# schematic.net
KiCad netlist of a schematic drawn in EAGLE
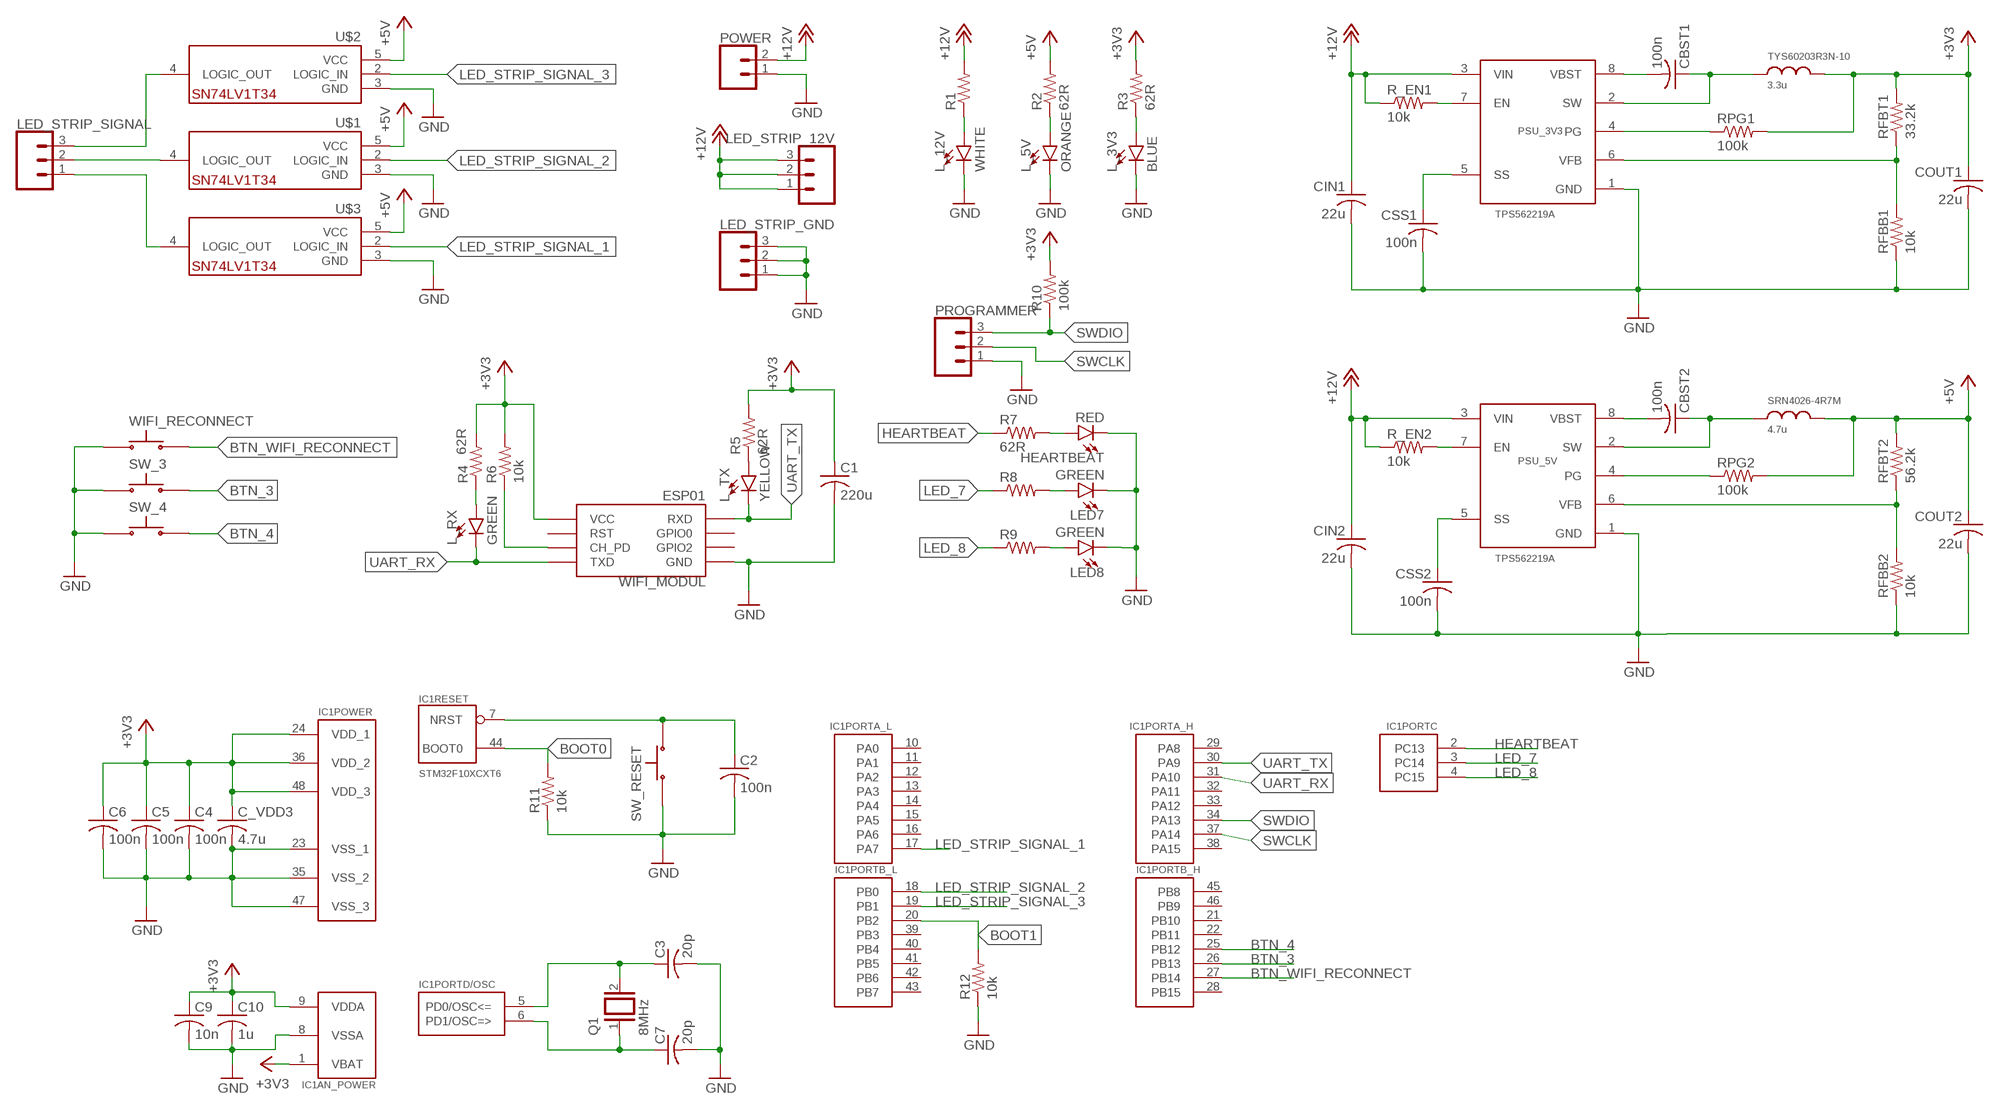
[diagram p0: schematic, sheet 1]

(export (version "E")
  (design (tool "Eeschema 10.0.6"))
  (components
    (comp (ref "C1")
      (value "220u")
      (footprint "eagle-import:C1206")
      (libsource (lib "eagle-import") (part "C-USC1206"))
    )
    (comp (ref "C2")
      (value "100n")
      (footprint "eagle-import:C1206")
      (libsource (lib "eagle-import") (part "C-USC1206"))
    )
    (comp (ref "C3")
      (value "20p")
      (footprint "eagle-import:C1206")
      (libsource (lib "eagle-import") (part "C-USC1206"))
    )
    (comp (ref "C4")
      (value "100n")
      (footprint "eagle-import:C1206")
      (libsource (lib "eagle-import") (part "C-USC1206"))
    )
    (comp (ref "C5")
      (value "100n")
      (footprint "eagle-import:C1206")
      (libsource (lib "eagle-import") (part "C-USC1206"))
    )
    (comp (ref "C6")
      (value "100n")
      (footprint "eagle-import:C1206")
      (libsource (lib "eagle-import") (part "C-USC1206"))
    )
    (comp (ref "C7")
      (value "20p")
      (footprint "eagle-import:C1206")
      (libsource (lib "eagle-import") (part "C-USC1206"))
    )
    (comp (ref "C9")
      (value "10n")
      (footprint "eagle-import:C1206")
      (libsource (lib "eagle-import") (part "C-USC1206"))
    )
    (comp (ref "C10")
      (value "1u")
      (footprint "eagle-import:C1206")
      (libsource (lib "eagle-import") (part "C-USC1206"))
    )
    (comp (ref "CBST1")
      (value "100n")
      (footprint "eagle-import:C1206")
      (libsource (lib "eagle-import") (part "C-USC1206"))
    )
    (comp (ref "CBST2")
      (value "100n")
      (footprint "eagle-import:C1206")
      (libsource (lib "eagle-import") (part "C-USC1206"))
    )
    (comp (ref "CIN1")
      (value "22u")
      (footprint "eagle-import:C1206")
      (libsource (lib "eagle-import") (part "C-USC1206"))
    )
    (comp (ref "CIN2")
      (value "22u")
      (footprint "eagle-import:C1206")
      (libsource (lib "eagle-import") (part "C-USC1206"))
    )
    (comp (ref "COUT1")
      (value "22u")
      (footprint "eagle-import:C1206")
      (libsource (lib "eagle-import") (part "C-USC1206"))
    )
    (comp (ref "COUT2")
      (value "22u")
      (footprint "eagle-import:C1206")
      (libsource (lib "eagle-import") (part "C-USC1206"))
    )
    (comp (ref "CSS1")
      (value "100n")
      (footprint "eagle-import:C1206")
      (libsource (lib "eagle-import") (part "C-USC1206"))
    )
    (comp (ref "CSS2")
      (value "100n")
      (footprint "eagle-import:C1206")
      (libsource (lib "eagle-import") (part "C-USC1206"))
    )
    (comp (ref "C_VDD3")
      (value "4.7u")
      (footprint "eagle-import:C1206")
      (libsource (lib "eagle-import") (part "C-USC1206"))
    )
    (comp (ref "HEARTBEAT")
      (value "RED")
      (footprint "eagle-import:LED-1206")
      (libsource (lib "eagle-import") (part "LED-GREEN1206"))
    )
    (comp (ref "IC1")
      (value "STM32F10XCXT6")
      (footprint "eagle-import:TQFP48")
      (libsource (lib "eagle-import") (part "STM32F10XCXT6"))
    )
    (comp (ref "LED7")
      (value "GREEN")
      (footprint "eagle-import:LED-1206")
      (libsource (lib "eagle-import") (part "LED-GREEN1206"))
    )
    (comp (ref "LED8")
      (value "GREEN")
      (footprint "eagle-import:LED-1206")
      (libsource (lib "eagle-import") (part "LED-GREEN1206"))
    )
    (comp (ref "LED_STRIP_12V")
      (value "CONN_03SCREW")
      (footprint "eagle-import:SCREWTERMINAL-3.5MM-3")
      (libsource (lib "eagle-import") (part "CONN_03SCREW"))
    )
    (comp (ref "LED_STRIP_GND")
      (value "CONN_03SCREW")
      (footprint "eagle-import:SCREWTERMINAL-3.5MM-3")
      (libsource (lib "eagle-import") (part "CONN_03SCREW"))
    )
    (comp (ref "LED_STRIP_SIGNAL")
      (value "CONN_03SCREW")
      (footprint "eagle-import:SCREWTERMINAL-3.5MM-3")
      (libsource (lib "eagle-import") (part "CONN_03SCREW"))
    )
    (comp (ref "L_3V3")
      (value "BLUE")
      (footprint "eagle-import:LED-1206")
      (libsource (lib "eagle-import") (part "LED-GREEN1206"))
    )
    (comp (ref "L_5V")
      (value "ORANGE")
      (footprint "eagle-import:LED-1206")
      (libsource (lib "eagle-import") (part "LED-GREEN1206"))
    )
    (comp (ref "L_12V")
      (value "WHITE")
      (footprint "eagle-import:LED-1206")
      (libsource (lib "eagle-import") (part "LED-GREEN1206"))
    )
    (comp (ref "L_RX")
      (value "GREEN")
      (footprint "eagle-import:LED-1206")
      (libsource (lib "eagle-import") (part "LED-GREEN1206"))
    )
    (comp (ref "L_TX")
      (value "YELLOW")
      (footprint "eagle-import:LED-1206")
      (libsource (lib "eagle-import") (part "LED-GREEN1206"))
    )
    (comp (ref "POWER")
      (value "CONN_025MM")
      (footprint "eagle-import:SCREWTERMINAL-5MM-2")
      (libsource (lib "eagle-import") (part "CONN_025MM"))
    )
    (comp (ref "PROGRAMMER")
      (value "CONN_03POLAR")
      (footprint "eagle-import:MOLEX-1X3")
      (libsource (lib "eagle-import") (part "CONN_03POLAR"))
    )
    (comp (ref "PSU_3V3")
      (value "TPS562219A")
      (footprint "eagle-import:SOT23-8L")
      (libsource (lib "eagle-import") (part "TPS562219A"))
    )
    (comp (ref "PSU_5V")
      (value "TPS562219A")
      (footprint "eagle-import:SOT23-8L")
      (libsource (lib "eagle-import") (part "TPS562219A"))
    )
    (comp (ref "Q1")
      (value "8MHz")
      (footprint "eagle-import:QS")
      (libsource (lib "eagle-import") (part "XTAL/S"))
    )
    (comp (ref "R1")
      (value "R-US_R1206")
      (footprint "eagle-import:R1206")
      (libsource (lib "eagle-import") (part "R-US_R1206"))
    )
    (comp (ref "R2")
      (value "62R")
      (footprint "eagle-import:R1206")
      (libsource (lib "eagle-import") (part "R-US_R1206"))
    )
    (comp (ref "R3")
      (value "62R")
      (footprint "eagle-import:R1206")
      (libsource (lib "eagle-import") (part "R-US_R1206"))
    )
    (comp (ref "R4")
      (value "62R")
      (footprint "eagle-import:R1206")
      (libsource (lib "eagle-import") (part "R-US_R1206"))
    )
    (comp (ref "R5")
      (value "62R")
      (footprint "eagle-import:R1206")
      (libsource (lib "eagle-import") (part "R-US_R1206"))
    )
    (comp (ref "R6")
      (value "10k")
      (footprint "eagle-import:R1206")
      (libsource (lib "eagle-import") (part "R-US_R1206"))
    )
    (comp (ref "R7")
      (value "62R")
      (footprint "eagle-import:R1206")
      (libsource (lib "eagle-import") (part "R-US_R1206"))
    )
    (comp (ref "R8")
      (value "R-US_R1206")
      (footprint "eagle-import:R1206")
      (libsource (lib "eagle-import") (part "R-US_R1206"))
    )
    (comp (ref "R9")
      (value "R-US_R1206")
      (footprint "eagle-import:R1206")
      (libsource (lib "eagle-import") (part "R-US_R1206"))
    )
    (comp (ref "R10")
      (value "100k")
      (footprint "eagle-import:R1206")
      (libsource (lib "eagle-import") (part "R-US_R1206"))
    )
    (comp (ref "R11")
      (value "10k")
      (footprint "eagle-import:R1206")
      (libsource (lib "eagle-import") (part "R-US_R1206"))
    )
    (comp (ref "R12")
      (value "10k")
      (footprint "eagle-import:R1206")
      (libsource (lib "eagle-import") (part "R-US_R1206"))
    )
    (comp (ref "RFBB1")
      (value "10k")
      (footprint "eagle-import:R1206")
      (libsource (lib "eagle-import") (part "R-US_R1206"))
    )
    (comp (ref "RFBB2")
      (value "10k")
      (footprint "eagle-import:R1206")
      (libsource (lib "eagle-import") (part "R-US_R1206"))
    )
    (comp (ref "RFBT1")
      (value "33.2k")
      (footprint "eagle-import:R1206")
      (libsource (lib "eagle-import") (part "R-US_R1206"))
    )
    (comp (ref "RFBT2")
      (value "56.2k")
      (footprint "eagle-import:R1206")
      (libsource (lib "eagle-import") (part "R-US_R1206"))
    )
    (comp (ref "RPG1")
      (value "100k")
      (footprint "eagle-import:R1206")
      (libsource (lib "eagle-import") (part "R-US_R1206"))
    )
    (comp (ref "RPG2")
      (value "100k")
      (footprint "eagle-import:R1206")
      (libsource (lib "eagle-import") (part "R-US_R1206"))
    )
    (comp (ref "R_EN1")
      (value "10k")
      (footprint "eagle-import:R1206")
      (libsource (lib "eagle-import") (part "R-US_R1206"))
    )
    (comp (ref "R_EN2")
      (value "10k")
      (footprint "eagle-import:R1206")
      (libsource (lib "eagle-import") (part "R-US_R1206"))
    )
    (comp (ref "SRN4026-4R7M")
      (value "4.7u")
      (footprint "eagle-import:SRN4026-4R7M")
      (libsource (lib "eagle-import") (part "SRN4026-4R7M"))
    )
    (comp (ref "SW_3")
      (value "TACTILE_SWITCH_SIDETACTILE_SWITCH_SIDE")
      (footprint "eagle-import:TACTILE_SWITCH_SIDE")
      (libsource (lib "eagle-import") (part "TACTILE_SWITCH_SIDETACTILE_SWITCH_SIDE"))
    )
    (comp (ref "SW_4")
      (value "TACTILE_SWITCH_SIDETACTILE_SWITCH_SIDE")
      (footprint "eagle-import:TACTILE_SWITCH_SIDE")
      (libsource (lib "eagle-import") (part "TACTILE_SWITCH_SIDETACTILE_SWITCH_SIDE"))
    )
    (comp (ref "SW_RESET")
      (value "TACTILE_SWITCH_SIDETACTILE_SWITCH_SIDE")
      (footprint "eagle-import:TACTILE_SWITCH_SIDE")
      (libsource (lib "eagle-import") (part "TACTILE_SWITCH_SIDETACTILE_SWITCH_SIDE"))
    )
    (comp (ref "TYS60203R3N-10")
      (value "3.3u")
      (footprint "eagle-import:TYS60203R3N-10")
      (libsource (lib "eagle-import") (part "TYS60203R3N-10"))
    )
    (comp (ref "U$1")
      (value "SN74LV1T34")
      (footprint "eagle-import:SOT-23-5")
      (libsource (lib "eagle-import") (part "SN74LV1T34"))
    )
    (comp (ref "U$2")
      (value "SN74LV1T34")
      (footprint "eagle-import:SOT-23-5")
      (fields (field (name "SPICEPREFIX") "U"))
      (libsource (lib "eagle-import") (part "SN74LV1T34"))
    )
    (comp (ref "U$3")
      (value "SN74LV1T34")
      (footprint "eagle-import:SOT-23-5")
      (libsource (lib "eagle-import") (part "SN74LV1T34"))
    )
    (comp (ref "WIFI_MODUL")
      (value "ESP01")
      (footprint "eagle-import:ESP01")
      (libsource (lib "eagle-import") (part "ESP01"))
    )
    (comp (ref "WIFI_RECONNECT")
      (value "TACTILE_SWITCH_SIDETACTILE_SWITCH_SIDE")
      (footprint "eagle-import:TACTILE_SWITCH_SIDE")
      (libsource (lib "eagle-import") (part "TACTILE_SWITCH_SIDETACTILE_SWITCH_SIDE"))
    )
  )
  (nets
    (net (code "1") (name "+3V3") (class "Default")
      (node (ref "C1") (pin "1") (pinfunction "1_1") (pintype "passive"))
      (node (ref "C10") (pin "1") (pinfunction "1_1") (pintype "passive"))
      (node (ref "C4") (pin "1") (pinfunction "1_1") (pintype "passive"))
      (node (ref "C5") (pin "1") (pinfunction "1_1") (pintype "passive"))
      (node (ref "C6") (pin "1") (pinfunction "1_1") (pintype "passive"))
      (node (ref "C9") (pin "1") (pinfunction "1_1") (pintype "passive"))
      (node (ref "COUT1") (pin "1") (pinfunction "1_1") (pintype "passive"))
      (node (ref "C_VDD3") (pin "1") (pinfunction "1_1") (pintype "passive"))
      (node (ref "IC1") (pin "1") (pinfunction "VBAT_1") (pintype "power_in"))
      (node (ref "IC1") (pin "24") (pinfunction "VDD_1_24") (pintype "power_in"))
      (node (ref "IC1") (pin "36") (pinfunction "VDD_2_36") (pintype "power_in"))
      (node (ref "IC1") (pin "48") (pinfunction "VDD_3_48") (pintype "power_in"))
      (node (ref "IC1") (pin "9") (pinfunction "VDDA_9") (pintype "power_in"))
      (node (ref "R10") (pin "2") (pinfunction "2_2") (pintype "passive"))
      (node (ref "R3") (pin "2") (pinfunction "2_2") (pintype "passive"))
      (node (ref "R4") (pin "2") (pinfunction "2_2") (pintype "passive"))
      (node (ref "R5") (pin "2") (pinfunction "2_2") (pintype "passive"))
      (node (ref "R6") (pin "2") (pinfunction "2_2") (pintype "passive"))
      (node (ref "RFBT1") (pin "2") (pinfunction "2_2") (pintype "passive"))
      (node (ref "RPG1") (pin "2") (pinfunction "2_2") (pintype "passive"))
      (node (ref "TYS60203R3N-10") (pin "P$2") (pinfunction "2_P$2") (pintype "passive"))
      (node (ref "WIFI_MODUL") (pin "VCC") (pinfunction "VCC_VCC") (pintype "bidirectional"))
    )
    (net (code "2") (name "+5V") (class "Default")
      (node (ref "COUT2") (pin "1") (pinfunction "1_1") (pintype "passive"))
      (node (ref "R2") (pin "2") (pinfunction "2_2") (pintype "passive"))
      (node (ref "RFBT2") (pin "2") (pinfunction "2_2") (pintype "passive"))
      (node (ref "RPG2") (pin "2") (pinfunction "2_2") (pintype "passive"))
      (node (ref "SRN4026-4R7M") (pin "P$3") (pinfunction "2_P$3") (pintype "passive"))
      (node (ref "U$1") (pin "5") (pinfunction "VCC_5") (pintype "bidirectional"))
      (node (ref "U$2") (pin "5") (pinfunction "VCC_5") (pintype "bidirectional"))
      (node (ref "U$3") (pin "5") (pinfunction "VCC_5") (pintype "bidirectional"))
    )
    (net (code "3") (name "+12V") (class "Default")
      (node (ref "CIN1") (pin "1") (pinfunction "1_1") (pintype "passive"))
      (node (ref "CIN2") (pin "1") (pinfunction "1_1") (pintype "passive"))
      (node (ref "LED_STRIP_12V") (pin "1") (pinfunction "1_1") (pintype "passive"))
      (node (ref "LED_STRIP_12V") (pin "2") (pinfunction "2_2") (pintype "passive"))
      (node (ref "LED_STRIP_12V") (pin "3") (pinfunction "3_3") (pintype "passive"))
      (node (ref "POWER") (pin "2") (pinfunction "2_2") (pintype "passive"))
      (node (ref "PSU_3V3") (pin "3") (pinfunction "VIN_3") (pintype "bidirectional"))
      (node (ref "PSU_5V") (pin "3") (pinfunction "VIN_3") (pintype "bidirectional"))
      (node (ref "R1") (pin "2") (pinfunction "2_2") (pintype "passive"))
      (node (ref "R_EN1") (pin "1") (pinfunction "1_1") (pintype "passive"))
      (node (ref "R_EN2") (pin "1") (pinfunction "1_1") (pintype "passive"))
    )
    (net (code "4") (name "BOOT0") (class "Default")
      (node (ref "IC1") (pin "44") (pinfunction "BOOT0_44") (pintype "input"))
      (node (ref "R11") (pin "2") (pinfunction "2_2") (pintype "passive"))
    )
    (net (code "5") (name "BOOT1") (class "Default")
      (node (ref "IC1") (pin "20") (pinfunction "PB2_20") (pintype "bidirectional"))
      (node (ref "R12") (pin "2") (pinfunction "2_2") (pintype "passive"))
    )
    (net (code "6") (name "BTN_3") (class "Default")
      (node (ref "IC1") (pin "26") (pinfunction "PB13_26") (pintype "bidirectional"))
      (node (ref "SW_3") (pin "P$5") (pinfunction "P$4_P$5") (pintype "bidirectional"))
    )
    (net (code "7") (name "BTN_4") (class "Default")
      (node (ref "IC1") (pin "25") (pinfunction "PB12_25") (pintype "bidirectional"))
      (node (ref "SW_4") (pin "P$5") (pinfunction "P$4_P$5") (pintype "bidirectional"))
    )
    (net (code "8") (name "BTN_WIFI_RECONNECT") (class "Default")
      (node (ref "IC1") (pin "27") (pinfunction "PB14_27") (pintype "bidirectional"))
      (node (ref "WIFI_RECONNECT") (pin "P$5") (pinfunction "P$4_P$5") (pintype "bidirectional"))
    )
    (net (code "9") (name "GND") (class "Default")
      (node (ref "C1") (pin "2") (pinfunction "2_2") (pintype "passive"))
      (node (ref "C10") (pin "2") (pinfunction "2_2") (pintype "passive"))
      (node (ref "C2") (pin "2") (pinfunction "2_2") (pintype "passive"))
      (node (ref "C3") (pin "2") (pinfunction "2_2") (pintype "passive"))
      (node (ref "C4") (pin "2") (pinfunction "2_2") (pintype "passive"))
      (node (ref "C5") (pin "2") (pinfunction "2_2") (pintype "passive"))
      (node (ref "C6") (pin "2") (pinfunction "2_2") (pintype "passive"))
      (node (ref "C7") (pin "2") (pinfunction "2_2") (pintype "passive"))
      (node (ref "C9") (pin "2") (pinfunction "2_2") (pintype "passive"))
      (node (ref "CIN1") (pin "2") (pinfunction "2_2") (pintype "passive"))
      (node (ref "CIN2") (pin "2") (pinfunction "2_2") (pintype "passive"))
      (node (ref "COUT1") (pin "2") (pinfunction "2_2") (pintype "passive"))
      (node (ref "COUT2") (pin "2") (pinfunction "2_2") (pintype "passive"))
      (node (ref "CSS1") (pin "2") (pinfunction "2_2") (pintype "passive"))
      (node (ref "CSS2") (pin "2") (pinfunction "2_2") (pintype "passive"))
      (node (ref "C_VDD3") (pin "2") (pinfunction "2_2") (pintype "passive"))
      (node (ref "HEARTBEAT") (pin "C") (pinfunction "C_C") (pintype "passive"))
      (node (ref "IC1") (pin "23") (pinfunction "VSS_1_23") (pintype "power_in"))
      (node (ref "IC1") (pin "35") (pinfunction "VSS_2_35") (pintype "power_in"))
      (node (ref "IC1") (pin "47") (pinfunction "VSS_3_47") (pintype "power_in"))
      (node (ref "IC1") (pin "8") (pinfunction "VSSA_8") (pintype "power_in"))
      (node (ref "LED7") (pin "C") (pinfunction "C_C") (pintype "passive"))
      (node (ref "LED8") (pin "C") (pinfunction "C_C") (pintype "passive"))
      (node (ref "LED_STRIP_GND") (pin "1") (pinfunction "1_1") (pintype "passive"))
      (node (ref "LED_STRIP_GND") (pin "2") (pinfunction "2_2") (pintype "passive"))
      (node (ref "LED_STRIP_GND") (pin "3") (pinfunction "3_3") (pintype "passive"))
      (node (ref "L_12V") (pin "C") (pinfunction "C_C") (pintype "passive"))
      (node (ref "L_3V3") (pin "C") (pinfunction "C_C") (pintype "passive"))
      (node (ref "L_5V") (pin "C") (pinfunction "C_C") (pintype "passive"))
      (node (ref "POWER") (pin "1") (pinfunction "1_1") (pintype "passive"))
      (node (ref "PROGRAMMER") (pin "1") (pinfunction "1_1") (pintype "passive"))
      (node (ref "PSU_3V3") (pin "1") (pinfunction "GND_1") (pintype "bidirectional"))
      (node (ref "PSU_5V") (pin "1") (pinfunction "GND_1") (pintype "bidirectional"))
      (node (ref "R11") (pin "1") (pinfunction "1_1") (pintype "passive"))
      (node (ref "R12") (pin "1") (pinfunction "1_1") (pintype "passive"))
      (node (ref "RFBB1") (pin "1") (pinfunction "1_1") (pintype "passive"))
      (node (ref "RFBB2") (pin "1") (pinfunction "1_1") (pintype "passive"))
      (node (ref "SW_3") (pin "P$3") (pinfunction "P$3_P$3") (pintype "bidirectional"))
      (node (ref "SW_4") (pin "P$3") (pinfunction "P$3_P$3") (pintype "bidirectional"))
      (node (ref "SW_RESET") (pin "P$5") (pinfunction "P$4_P$5") (pintype "bidirectional"))
      (node (ref "U$1") (pin "3") (pinfunction "GND_3") (pintype "bidirectional"))
      (node (ref "U$2") (pin "3") (pinfunction "GND_3") (pintype "bidirectional"))
      (node (ref "U$3") (pin "3") (pinfunction "GND_3") (pintype "bidirectional"))
      (node (ref "WIFI_MODUL") (pin "GND") (pinfunction "GND_GND") (pintype "bidirectional"))
      (node (ref "WIFI_RECONNECT") (pin "P$3") (pinfunction "P$3_P$3") (pintype "bidirectional"))
    )
    (net (code "10") (name "HEARTBEAT") (class "Default")
      (node (ref "IC1") (pin "2") (pinfunction "PC13_2") (pintype "bidirectional"))
      (node (ref "R7") (pin "1") (pinfunction "1_1") (pintype "passive"))
    )
    (net (code "11") (name "LED_7") (class "Default")
      (node (ref "IC1") (pin "3") (pinfunction "PC14_3") (pintype "bidirectional"))
      (node (ref "R8") (pin "1") (pinfunction "1_1") (pintype "passive"))
    )
    (net (code "12") (name "LED_8") (class "Default")
      (node (ref "IC1") (pin "4") (pinfunction "PC15_4") (pintype "bidirectional"))
      (node (ref "R9") (pin "1") (pinfunction "1_1") (pintype "passive"))
    )
    (net (code "13") (name "LED_STRIP_SIGNAL_1") (class "Default")
      (node (ref "IC1") (pin "17") (pinfunction "PA7_17") (pintype "bidirectional"))
      (node (ref "U$3") (pin "2") (pinfunction "LOGIC_IN_2") (pintype "bidirectional"))
    )
    (net (code "14") (name "LED_STRIP_SIGNAL_2") (class "Default")
      (node (ref "IC1") (pin "18") (pinfunction "PB0_18") (pintype "bidirectional"))
      (node (ref "U$1") (pin "2") (pinfunction "LOGIC_IN_2") (pintype "bidirectional"))
    )
    (net (code "15") (name "LED_STRIP_SIGNAL_3") (class "Default")
      (node (ref "IC1") (pin "19") (pinfunction "PB1_19") (pintype "bidirectional"))
      (node (ref "U$2") (pin "2") (pinfunction "LOGIC_IN_2") (pintype "bidirectional"))
    )
    (net (code "16") (name "Net-(HEARTBEAT-PadA)") (class "Default")
      (node (ref "HEARTBEAT") (pin "A") (pinfunction "A_A") (pintype "passive"))
      (node (ref "R7") (pin "2") (pinfunction "2_2") (pintype "passive"))
    )
    (net (code "17") (name "Net-(IC1G-PD0{slash}OSC<=)") (class "Default")
      (node (ref "C3") (pin "1") (pinfunction "1_1") (pintype "passive"))
      (node (ref "IC1") (pin "5") (pinfunction "PD0/OSC<=_5") (pintype "bidirectional"))
      (node (ref "Q1") (pin "2") (pinfunction "2_2") (pintype "passive"))
    )
    (net (code "18") (name "Net-(IC1G-PD1{slash}OSC=>)") (class "Default")
      (node (ref "C7") (pin "1") (pinfunction "1_1") (pintype "passive"))
      (node (ref "IC1") (pin "6") (pinfunction "PD1/OSC=>_6") (pintype "bidirectional"))
      (node (ref "Q1") (pin "1") (pinfunction "1_1") (pintype "passive"))
    )
    (net (code "19") (name "Net-(IC1I-NRST)") (class "Default")
      (node (ref "C2") (pin "1") (pinfunction "1_1") (pintype "passive"))
      (node (ref "IC1") (pin "7") (pinfunction "NRST_7") (pintype "input"))
      (node (ref "SW_RESET") (pin "P$3") (pinfunction "P$3_P$3") (pintype "bidirectional"))
    )
    (net (code "20") (name "Net-(LED7-PadA)") (class "Default")
      (node (ref "LED7") (pin "A") (pinfunction "A_A") (pintype "passive"))
      (node (ref "R8") (pin "2") (pinfunction "2_2") (pintype "passive"))
    )
    (net (code "21") (name "Net-(LED8-PadA)") (class "Default")
      (node (ref "LED8") (pin "A") (pinfunction "A_A") (pintype "passive"))
      (node (ref "R9") (pin "2") (pinfunction "2_2") (pintype "passive"))
    )
    (net (code "22") (name "Net-(L_3V3-PadA)") (class "Default")
      (node (ref "L_3V3") (pin "A") (pinfunction "A_A") (pintype "passive"))
      (node (ref "R3") (pin "1") (pinfunction "1_1") (pintype "passive"))
    )
    (net (code "23") (name "Net-(L_5V-PadA)") (class "Default")
      (node (ref "L_5V") (pin "A") (pinfunction "A_A") (pintype "passive"))
      (node (ref "R2") (pin "1") (pinfunction "1_1") (pintype "passive"))
    )
    (net (code "24") (name "Net-(L_12V-PadA)") (class "Default")
      (node (ref "L_12V") (pin "A") (pinfunction "A_A") (pintype "passive"))
      (node (ref "R1") (pin "1") (pinfunction "1_1") (pintype "passive"))
    )
    (net (code "25") (name "Net-(L_RX-PadA)") (class "Default")
      (node (ref "L_RX") (pin "A") (pinfunction "A_A") (pintype "passive"))
      (node (ref "R4") (pin "1") (pinfunction "1_1") (pintype "passive"))
    )
    (net (code "26") (name "Net-(L_TX-PadA)") (class "Default")
      (node (ref "L_TX") (pin "A") (pinfunction "A_A") (pintype "passive"))
      (node (ref "R5") (pin "1") (pinfunction "1_1") (pintype "passive"))
    )
    (net (code "27") (name "Net-(PSU_3V3-EN)") (class "Default")
      (node (ref "PSU_3V3") (pin "7") (pinfunction "EN_7") (pintype "bidirectional"))
      (node (ref "R_EN1") (pin "2") (pinfunction "2_2") (pintype "passive"))
    )
    (net (code "28") (name "Net-(PSU_3V3-PG)") (class "Default")
      (node (ref "PSU_3V3") (pin "4") (pinfunction "PG_4") (pintype "bidirectional"))
      (node (ref "RPG1") (pin "1") (pinfunction "1_1") (pintype "passive"))
    )
    (net (code "29") (name "Net-(PSU_3V3-SS)") (class "Default")
      (node (ref "CSS1") (pin "1") (pinfunction "1_1") (pintype "passive"))
      (node (ref "PSU_3V3") (pin "5") (pinfunction "SS_5") (pintype "bidirectional"))
    )
    (net (code "30") (name "Net-(PSU_3V3-SW)") (class "Default")
      (node (ref "CBST1") (pin "1") (pinfunction "1_1") (pintype "passive"))
      (node (ref "PSU_3V3") (pin "2") (pinfunction "SW_2") (pintype "bidirectional"))
      (node (ref "TYS60203R3N-10") (pin "P$1") (pinfunction "1_P$1") (pintype "passive"))
    )
    (net (code "31") (name "Net-(PSU_3V3-VBST)") (class "Default")
      (node (ref "CBST1") (pin "2") (pinfunction "2_2") (pintype "passive"))
      (node (ref "PSU_3V3") (pin "8") (pinfunction "VBST_8") (pintype "bidirectional"))
    )
    (net (code "32") (name "Net-(PSU_3V3-VFB)") (class "Default")
      (node (ref "PSU_3V3") (pin "6") (pinfunction "VFB_6") (pintype "bidirectional"))
      (node (ref "RFBB1") (pin "2") (pinfunction "2_2") (pintype "passive"))
      (node (ref "RFBT1") (pin "1") (pinfunction "1_1") (pintype "passive"))
    )
    (net (code "33") (name "Net-(PSU_5V-EN)") (class "Default")
      (node (ref "PSU_5V") (pin "7") (pinfunction "EN_7") (pintype "bidirectional"))
      (node (ref "R_EN2") (pin "2") (pinfunction "2_2") (pintype "passive"))
    )
    (net (code "34") (name "Net-(PSU_5V-PG)") (class "Default")
      (node (ref "PSU_5V") (pin "4") (pinfunction "PG_4") (pintype "bidirectional"))
      (node (ref "RPG2") (pin "1") (pinfunction "1_1") (pintype "passive"))
    )
    (net (code "35") (name "Net-(PSU_5V-SS)") (class "Default")
      (node (ref "CSS2") (pin "1") (pinfunction "1_1") (pintype "passive"))
      (node (ref "PSU_5V") (pin "5") (pinfunction "SS_5") (pintype "bidirectional"))
    )
    (net (code "36") (name "Net-(PSU_5V-SW)") (class "Default")
      (node (ref "CBST2") (pin "1") (pinfunction "1_1") (pintype "passive"))
      (node (ref "PSU_5V") (pin "2") (pinfunction "SW_2") (pintype "bidirectional"))
      (node (ref "SRN4026-4R7M") (pin "P$2") (pinfunction "1_P$2") (pintype "passive"))
    )
    (net (code "37") (name "Net-(PSU_5V-VBST)") (class "Default")
      (node (ref "CBST2") (pin "2") (pinfunction "2_2") (pintype "passive"))
      (node (ref "PSU_5V") (pin "8") (pinfunction "VBST_8") (pintype "bidirectional"))
    )
    (net (code "38") (name "Net-(PSU_5V-VFB)") (class "Default")
      (node (ref "PSU_5V") (pin "6") (pinfunction "VFB_6") (pintype "bidirectional"))
      (node (ref "RFBB2") (pin "2") (pinfunction "2_2") (pintype "passive"))
      (node (ref "RFBT2") (pin "1") (pinfunction "1_1") (pintype "passive"))
    )
    (net (code "39") (name "Net-(R6-Pad1)") (class "Default")
      (node (ref "R6") (pin "1") (pinfunction "1_1") (pintype "passive"))
      (node (ref "WIFI_MODUL") (pin "CH_PD") (pinfunction "CH_PD_CH_PD") (pintype "bidirectional"))
    )
    (net (code "40") (name "Net-(U$1-LOGIC_OUT)") (class "Default")
      (node (ref "LED_STRIP_SIGNAL") (pin "2") (pinfunction "2_2") (pintype "passive"))
      (node (ref "U$1") (pin "4") (pinfunction "LOGIC_OUT_4") (pintype "bidirectional"))
    )
    (net (code "41") (name "Net-(U$2-LOGIC_OUT)") (class "Default")
      (node (ref "LED_STRIP_SIGNAL") (pin "3") (pinfunction "3_3") (pintype "passive"))
      (node (ref "U$2") (pin "4") (pinfunction "LOGIC_OUT_4") (pintype "bidirectional"))
    )
    (net (code "42") (name "Net-(U$3-LOGIC_OUT)") (class "Default")
      (node (ref "LED_STRIP_SIGNAL") (pin "1") (pinfunction "1_1") (pintype "passive"))
      (node (ref "U$3") (pin "4") (pinfunction "LOGIC_OUT_4") (pintype "bidirectional"))
    )
    (net (code "43") (name "SWCLK") (class "Default")
      (node (ref "IC1") (pin "37") (pinfunction "PA14_37") (pintype "bidirectional"))
      (node (ref "PROGRAMMER") (pin "2") (pinfunction "2_2") (pintype "passive"))
    )
    (net (code "44") (name "SWDIO") (class "Default")
      (node (ref "IC1") (pin "34") (pinfunction "PA13_34") (pintype "bidirectional"))
      (node (ref "PROGRAMMER") (pin "3") (pinfunction "3_3") (pintype "passive"))
      (node (ref "R10") (pin "1") (pinfunction "1_1") (pintype "passive"))
    )
    (net (code "45") (name "UART_RX") (class "Default")
      (node (ref "IC1") (pin "31") (pinfunction "PA10_31") (pintype "bidirectional"))
      (node (ref "L_RX") (pin "C") (pinfunction "C_C") (pintype "passive"))
      (node (ref "WIFI_MODUL") (pin "TX") (pinfunction "TXD_TX") (pintype "bidirectional"))
    )
    (net (code "46") (name "UART_TX") (class "Default")
      (node (ref "IC1") (pin "30") (pinfunction "PA9_30") (pintype "bidirectional"))
      (node (ref "L_TX") (pin "C") (pinfunction "C_C") (pintype "passive"))
      (node (ref "WIFI_MODUL") (pin "RX") (pinfunction "RXD_RX") (pintype "bidirectional"))
    )
    (net (code "47") (name "unconnected-(IC1B-PA8-Pad29)") (class "Default")
      (node (ref "IC1") (pin "29") (pinfunction "PA8_29") (pintype "bidirectional"))
    )
    (net (code "48") (name "unconnected-(IC1B-PA11-Pad32)") (class "Default")
      (node (ref "IC1") (pin "32") (pinfunction "PA11_32") (pintype "bidirectional"))
    )
    (net (code "49") (name "unconnected-(IC1B-PA12-Pad33)") (class "Default")
      (node (ref "IC1") (pin "33") (pinfunction "PA12_33") (pintype "bidirectional"))
    )
    (net (code "50") (name "unconnected-(IC1B-PA15-Pad38)") (class "Default")
      (node (ref "IC1") (pin "38") (pinfunction "PA15_38") (pintype "bidirectional"))
    )
    (net (code "51") (name "unconnected-(IC1C-PA0-Pad10)") (class "Default")
      (node (ref "IC1") (pin "10") (pinfunction "PA0_10") (pintype "bidirectional"))
    )
    (net (code "52") (name "unconnected-(IC1C-PA1-Pad11)") (class "Default")
      (node (ref "IC1") (pin "11") (pinfunction "PA1_11") (pintype "bidirectional"))
    )
    (net (code "53") (name "unconnected-(IC1C-PA2-Pad12)") (class "Default")
      (node (ref "IC1") (pin "12") (pinfunction "PA2_12") (pintype "bidirectional"))
    )
    (net (code "54") (name "unconnected-(IC1C-PA3-Pad13)") (class "Default")
      (node (ref "IC1") (pin "13") (pinfunction "PA3_13") (pintype "bidirectional"))
    )
    (net (code "55") (name "unconnected-(IC1C-PA4-Pad14)") (class "Default")
      (node (ref "IC1") (pin "14") (pinfunction "PA4_14") (pintype "bidirectional"))
    )
    (net (code "56") (name "unconnected-(IC1C-PA5-Pad15)") (class "Default")
      (node (ref "IC1") (pin "15") (pinfunction "PA5_15") (pintype "bidirectional"))
    )
    (net (code "57") (name "unconnected-(IC1C-PA6-Pad16)") (class "Default")
      (node (ref "IC1") (pin "16") (pinfunction "PA6_16") (pintype "bidirectional"))
    )
    (net (code "58") (name "unconnected-(IC1D-PB8-Pad45)") (class "Default")
      (node (ref "IC1") (pin "45") (pinfunction "PB8_45") (pintype "bidirectional"))
    )
    (net (code "59") (name "unconnected-(IC1D-PB9-Pad46)") (class "Default")
      (node (ref "IC1") (pin "46") (pinfunction "PB9_46") (pintype "bidirectional"))
    )
    (net (code "60") (name "unconnected-(IC1D-PB10-Pad21)") (class "Default")
      (node (ref "IC1") (pin "21") (pinfunction "PB10_21") (pintype "bidirectional"))
    )
    (net (code "61") (name "unconnected-(IC1D-PB11-Pad22)") (class "Default")
      (node (ref "IC1") (pin "22") (pinfunction "PB11_22") (pintype "bidirectional"))
    )
    (net (code "62") (name "unconnected-(IC1D-PB15-Pad28)") (class "Default")
      (node (ref "IC1") (pin "28") (pinfunction "PB15_28") (pintype "bidirectional"))
    )
    (net (code "63") (name "unconnected-(IC1E-PB3-Pad39)") (class "Default")
      (node (ref "IC1") (pin "39") (pinfunction "PB3_39") (pintype "bidirectional"))
    )
    (net (code "64") (name "unconnected-(IC1E-PB4-Pad40)") (class "Default")
      (node (ref "IC1") (pin "40") (pinfunction "PB4_40") (pintype "bidirectional"))
    )
    (net (code "65") (name "unconnected-(IC1E-PB5-Pad41)") (class "Default")
      (node (ref "IC1") (pin "41") (pinfunction "PB5_41") (pintype "bidirectional"))
    )
    (net (code "66") (name "unconnected-(IC1E-PB6-Pad42)") (class "Default")
      (node (ref "IC1") (pin "42") (pinfunction "PB6_42") (pintype "bidirectional"))
    )
    (net (code "67") (name "unconnected-(IC1E-PB7-Pad43)") (class "Default")
      (node (ref "IC1") (pin "43") (pinfunction "PB7_43") (pintype "bidirectional"))
    )
    (net (code "68") (name "unconnected-(WIFI_MODUL-PadGPIO0)") (class "Default")
      (node (ref "WIFI_MODUL") (pin "GPIO0") (pinfunction "GPIO0_GPIO0") (pintype "bidirectional"))
    )
    (net (code "69") (name "unconnected-(WIFI_MODUL-PadGPIO2)") (class "Default")
      (node (ref "WIFI_MODUL") (pin "GPIO2") (pinfunction "GPIO2_GPIO2") (pintype "bidirectional"))
    )
    (net (code "70") (name "unconnected-(WIFI_MODUL-PadRST)") (class "Default")
      (node (ref "WIFI_MODUL") (pin "RST") (pinfunction "RST_RST") (pintype "bidirectional"))
    )
  )
)
